# Ethernet_Interface.net
KiCad netlist of a schematic drawn in Altium Designer
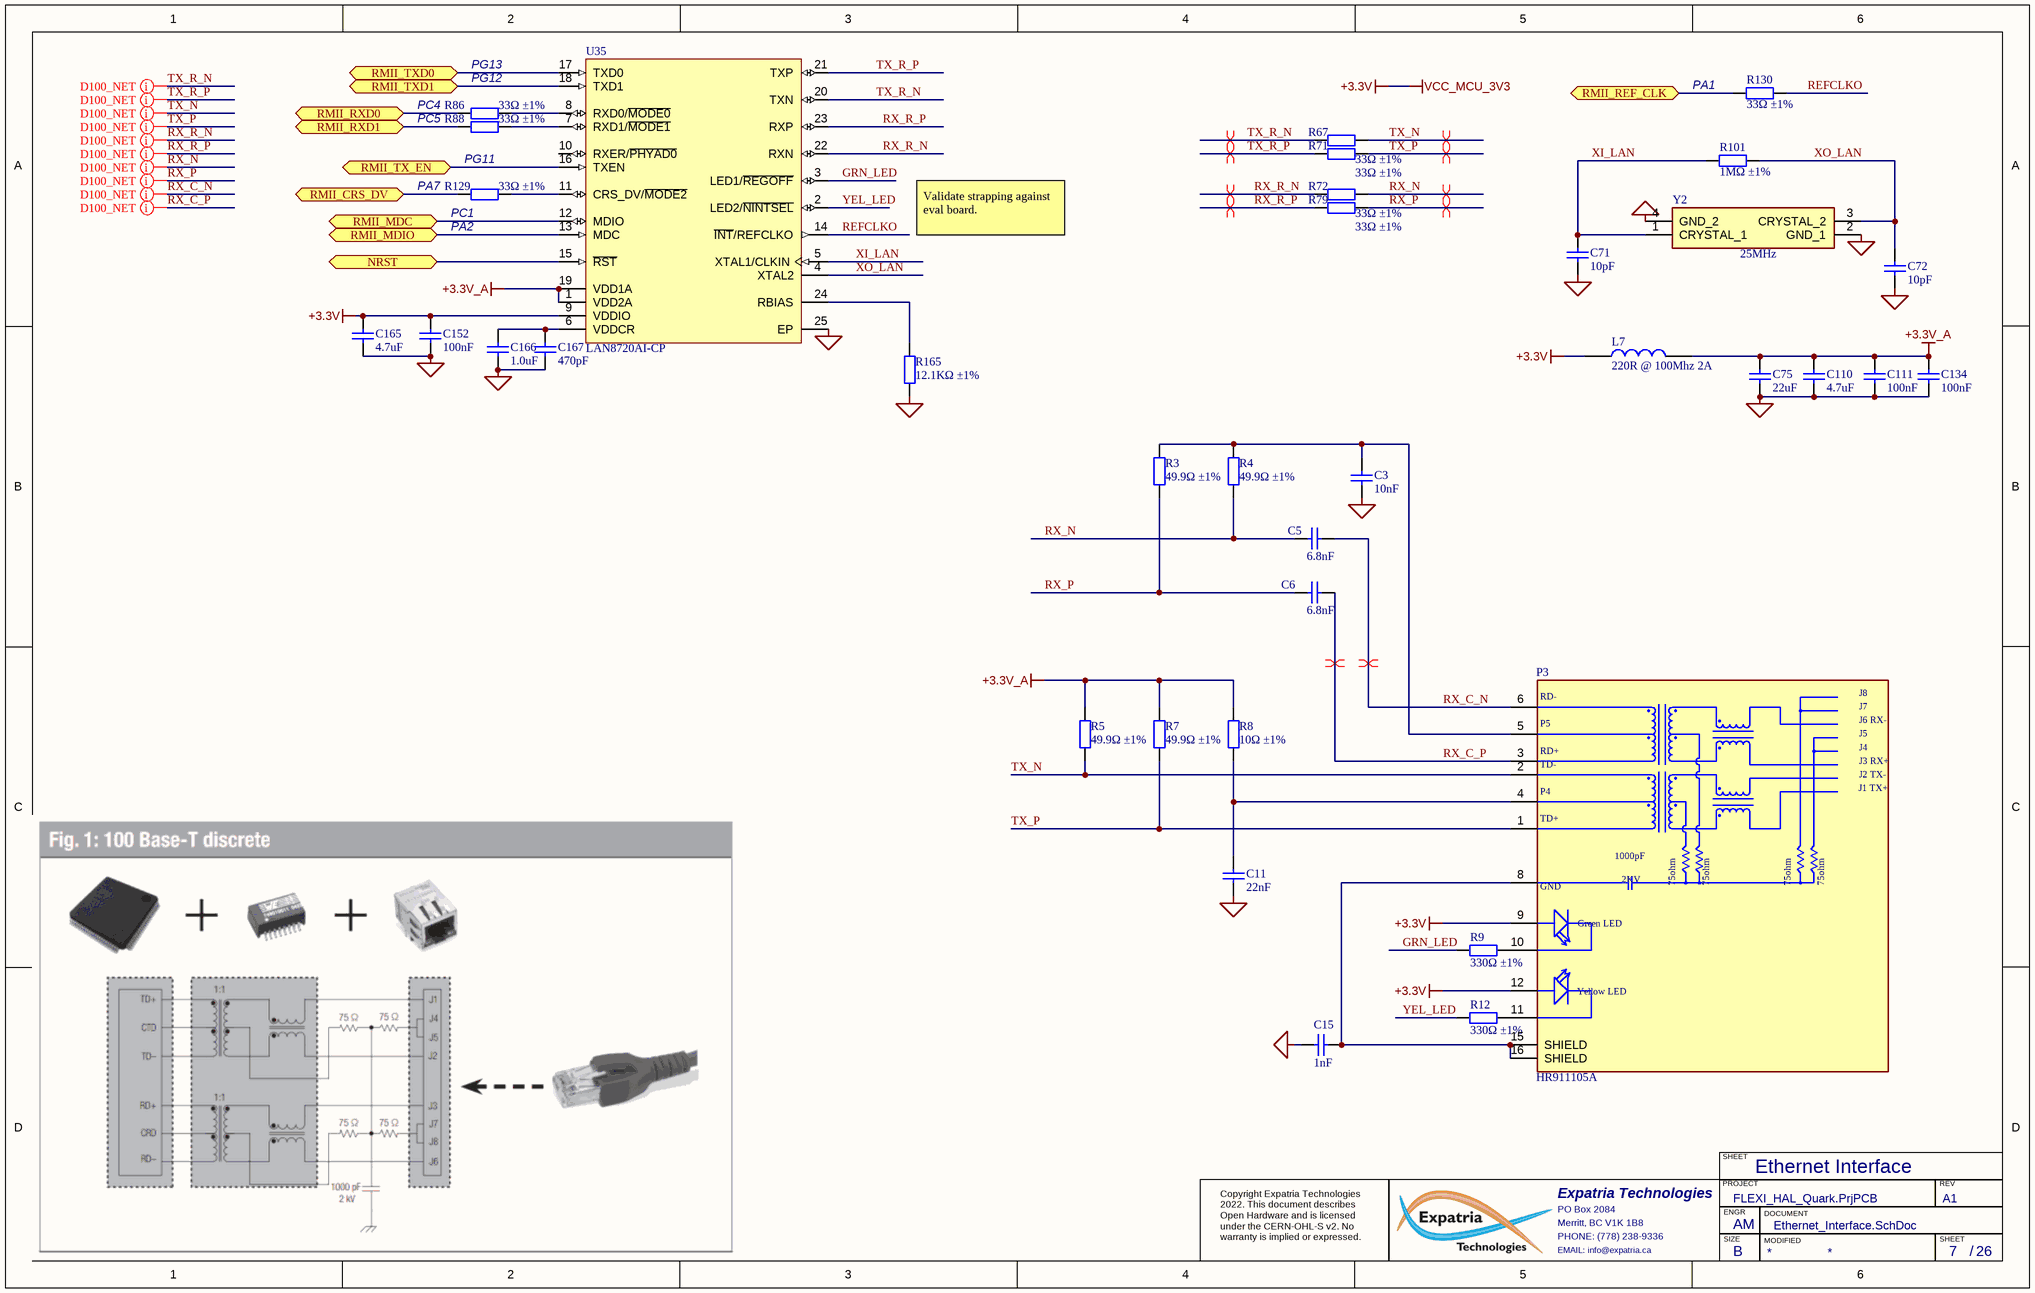
[diagram p0: Ethernet_Interface.SchDoc]

(export (version "E")
  (design (tool "Eeschema 10.0.6"))
  (components
    (comp (ref "C3")
      (value "10nF")
      (footprint "0402_C")
      (description "Chip capacitors")
      (fields
        (field (name "MANUFACTURER") "Samsung Electro-Mechanics")
        (field (name "MANUFACTURER PART NUMBER") "CL05B103KB5NNNC")
      )
      (libsource (lib "Cap") (part "0402 10nF (103) 10% 50V"))
    )
    (comp (ref "C5")
      (value "6.8nF")
      (footprint "0402_C")
      (description "Chip capacitors")
      (fields
        (field (name "MANUFACTURER") "Guangdong Fenghua Advanced Tech")
        (field (name "MANUFACTURER PART NUMBER") "0402B682K500NT")
      )
      (libsource (lib "Cap") (part "0402 6.8nF (682) 10% 50V"))
    )
    (comp (ref "C6")
      (value "6.8nF")
      (footprint "0402_C")
      (description "Chip capacitors")
      (fields
        (field (name "MANUFACTURER") "Guangdong Fenghua Advanced Tech")
        (field (name "MANUFACTURER PART NUMBER") "0402B682K500NT")
      )
      (libsource (lib "Cap") (part "0402 6.8nF (682) 10% 50V"))
    )
    (comp (ref "C11")
      (value "22nF")
      (footprint "0402_C")
      (description "Chip capacitors")
      (fields
        (field (name "MANUFACTURER") "Guangdong Fenghua Advanced Tech")
        (field (name "MANUFACTURER PART NUMBER") "0402B223K500NT")
      )
      (libsource (lib "Cap") (part "0402 22nF (223) 10% 50V"))
    )
    (comp (ref "C15")
      (value "1nF")
      (footprint "1206_C")
      (description "Chip capacitors")
      (fields
        (field (name "MANUFACTURER") "Samsung Electro-Mechanics")
        (field (name "MANUFACTURER PART NUMBER") "CL31B102KGFNNNE")
      )
      (libsource (lib "Cap") (part "1206 1nF (102) 10% 500V"))
    )
    (comp (ref "C71")
      (value "10pF")
      (footprint "0402_C")
      (description "Chip capacitors")
      (fields
        (field (name "MANUFACTURER") "Samsung Electro-Mechanics")
        (field (name "MANUFACTURER PART NUMBER") "CL05C100JB5NNNC")
      )
      (libsource (lib "Cap") (part "0402 10pF (100) 5% 50V"))
    )
    (comp (ref "C72")
      (value "10pF")
      (footprint "0402_C")
      (description "Chip capacitors")
      (fields
        (field (name "MANUFACTURER") "Samsung Electro-Mechanics")
        (field (name "MANUFACTURER PART NUMBER") "CL05C100JB5NNNC")
      )
      (libsource (lib "Cap") (part "0402 10pF (100) 5% 50V"))
    )
    (comp (ref "C75")
      (value "22uF")
      (footprint "0805_C")
      (description "25V 22uF X5R ±20% 0805 Multilayer Ceramic Capacitors MLCC - SMD/SMT ROHS")
      (fields (field (name "MANUFACTURER") "Samsung Electro-Mechanics") (field (name "TOLERANCE") "20%"))
      (libsource (lib "Sienci_Labs") (part "0805 22uF (226) 20% 25V"))
    )
    (comp (ref "C110")
      (value "4.7uF")
      (footprint "0603_C")
      (description "16V 4.7uF X5R ±10% 0603 Multilayer Ceramic Capacitors MLCC - SMD/SMT ROHS")
      (fields (field (name "MANUFACTURER") "Samsung Electro-Mechanics") (field (name "TOLERANCE") "10%"))
      (libsource (lib "Sienci_Labs") (part "0603 4.7uF (475) 10% 16V"))
    )
    (comp (ref "C111")
      (value "100nF")
      (footprint "0402_C")
      (description "16V 100nF X7R ±10% 0402 Multilayer Ceramic Capacitors MLCC - SMD/SMT ROHS")
      (fields (field (name "MANUFACTURER") "Samsung Electro-Mechanics") (field (name "TOLERANCE") "10%"))
      (libsource (lib "Sienci_Labs") (part "0402 100nF (104) 10% 16V"))
    )
    (comp (ref "C134")
      (value "100nF")
      (footprint "0402_C")
      (description "16V 100nF X7R ±10% 0402 Multilayer Ceramic Capacitors MLCC - SMD/SMT ROHS")
      (fields (field (name "MANUFACTURER") "Samsung Electro-Mechanics") (field (name "TOLERANCE") "10%"))
      (libsource (lib "Sienci_Labs") (part "0402 100nF (104) 10% 16V"))
    )
    (comp (ref "C152")
      (value "100nF")
      (footprint "0402_C")
      (description "16V 100nF X7R ±10% 0402 Multilayer Ceramic Capacitors MLCC - SMD/SMT ROHS")
      (fields (field (name "MANUFACTURER") "Samsung Electro-Mechanics") (field (name "TOLERANCE") "10%"))
      (libsource (lib "Sienci_Labs") (part "0402 100nF (104) 10% 16V"))
    )
    (comp (ref "C165")
      (value "4.7uF")
      (footprint "0603_C")
      (description "16V 4.7uF X5R ±10% 0603 Multilayer Ceramic Capacitors MLCC - SMD/SMT ROHS")
      (fields (field (name "MANUFACTURER") "Samsung Electro-Mechanics") (field (name "TOLERANCE") "10%"))
      (libsource (lib "Sienci_Labs") (part "0603 4.7uF (475) 10% 16V"))
    )
    (comp (ref "C166")
      (value "1.0uF")
      (footprint "0402_C")
      (description "Chip capacitor")
      (fields
        (field (name "MANUFACTURER") "Samsung Electro-Mechanics")
        (field (name "PARTNUMBER") "CL05A105KA5NQNC")
      )
      (libsource (lib "Cap") (part "0402 1.0uF (105) 10% 25V"))
    )
    (comp (ref "C167")
      (value "470pF")
      (footprint "0402_C")
      (description "Chip capacitors")
      (fields
        (field (name "MANUFACTURER") "Guangdong Fenghua Advanced Tech")
        (field (name "PARTNUMBER") "0402B471K500NT")
      )
      (libsource (lib "Cap") (part "0402 470pF (471) 10% 50V"))
    )
    (comp (ref "L7")
      (value "220R @ 100Mhz 2A")
      (footprint "0805_R")
      (description "150mΩ ±25% 220Ω@100MHz 0805 Ferrite Beads ROHS")
      (fields
        (field (name "MANUFACTURER PART NUMBER") "CBW201209U221T")
        (field (name "MANUFACTURER") "FH (Guangdong Fenghua Advanced Tech)")
      )
      (libsource (lib "Sienci_Labs") (part "CBW201209U221T"))
    )
    (comp (ref "P3")
      (value "HR911105A")
      (footprint "HANRUN_HR911105A")
      (description "HR911105A Ethernet Interface Arduino Platform Evaluation Expansion Board")
      (fields (field (name "MANUFACTURER") "DFRobot"))
      (libsource (lib "Sienci_Labs") (part "HR911105A"))
    )
    (comp (ref "R3")
      (value "49.9Ω ±1%")
      (footprint "0402_R")
      (description "Chip resistor")
      (fields
        (field (name "MANUFACTURER") "Uniroyal Elec")
        (field (name "MANUFACTURER PART NUMBER") "0402WGF499JTCE")
      )
      (libsource (lib "RES") (part "0402 49.9R (49R9) 1%"))
    )
    (comp (ref "R4")
      (value "49.9Ω ±1%")
      (footprint "0402_R")
      (description "Chip resistor")
      (fields
        (field (name "MANUFACTURER") "Uniroyal Elec")
        (field (name "MANUFACTURER PART NUMBER") "0402WGF499JTCE")
      )
      (libsource (lib "RES") (part "0402 49.9R (49R9) 1%"))
    )
    (comp (ref "R5")
      (value "49.9Ω ±1%")
      (footprint "0402_R")
      (description "Chip resistor")
      (fields
        (field (name "MANUFACTURER") "Uniroyal Elec")
        (field (name "MANUFACTURER PART NUMBER") "0402WGF499JTCE")
      )
      (libsource (lib "RES") (part "0402 49.9R (49R9) 1%"))
    )
    (comp (ref "R7")
      (value "49.9Ω ±1%")
      (footprint "0402_R")
      (description "Chip resistor")
      (fields
        (field (name "MANUFACTURER") "Uniroyal Elec")
        (field (name "MANUFACTURER PART NUMBER") "0402WGF499JTCE")
      )
      (libsource (lib "RES") (part "0402 49.9R (49R9) 1%"))
    )
    (comp (ref "R8")
      (value "10Ω ±1%")
      (footprint "0402_R")
      (description "Chip resistor")
      (fields
        (field (name "MANUFACTURER") "Uniroyal Elec")
        (field (name "MANUFACTURER PART NUMBER") "0402WGF100JTCE")
      )
      (libsource (lib "RES") (part "0402 10R (10R0) 1%"))
    )
    (comp (ref "R9")
      (value "330Ω ±1%")
      (footprint "0402_R")
      (description "Chip resistor")
      (fields
        (field (name "MANUFACTURER") "Uniroyal Elec")
        (field (name "MANUFACTURER PART NUMBER") "0402WGF3300TCE")
      )
      (libsource (lib "RES") (part "0402 330R (3300) 1%"))
    )
    (comp (ref "R12")
      (value "330Ω ±1%")
      (footprint "0402_R")
      (description "Chip resistor")
      (fields
        (field (name "MANUFACTURER") "Uniroyal Elec")
        (field (name "MANUFACTURER PART NUMBER") "0402WGF3300TCE")
      )
      (libsource (lib "RES") (part "0402 330R (3300) 1%"))
    )
    (comp (ref "R67")
      (value "33Ω ±1%")
      (footprint "0402_R")
      (description "Chip resistor")
      (fields
        (field (name "MANUFACTURER") "Uniroyal Elec")
        (field (name "MANUFACTURER PART NUMBER") "0402WGF330JTCE")
      )
      (libsource (lib "RES") (part "0402 33R (33R0) 1%"))
    )
    (comp (ref "R71")
      (value "33Ω ±1%")
      (footprint "0402_R")
      (description "Chip resistor")
      (fields
        (field (name "MANUFACTURER") "Uniroyal Elec")
        (field (name "MANUFACTURER PART NUMBER") "0402WGF330JTCE")
      )
      (libsource (lib "RES") (part "0402 33R (33R0) 1%"))
    )
    (comp (ref "R72")
      (value "33Ω ±1%")
      (footprint "0402_R")
      (description "Chip resistor")
      (fields
        (field (name "MANUFACTURER") "Uniroyal Elec")
        (field (name "MANUFACTURER PART NUMBER") "0402WGF330JTCE")
      )
      (libsource (lib "RES") (part "0402 33R (33R0) 1%"))
    )
    (comp (ref "R79")
      (value "33Ω ±1%")
      (footprint "0402_R")
      (description "Chip resistor")
      (fields
        (field (name "MANUFACTURER") "Uniroyal Elec")
        (field (name "MANUFACTURER PART NUMBER") "0402WGF330JTCE")
      )
      (libsource (lib "RES") (part "0402 33R (33R0) 1%"))
    )
    (comp (ref "R86")
      (value "33Ω ±1%")
      (footprint "0402_R")
      (description "Chip resistor")
      (fields
        (field (name "MANUFACTURER") "Uniroyal Elec")
        (field (name "MANUFACTURER PART NUMBER") "0402WGF330JTCE")
      )
      (libsource (lib "") (part "0402 33R (33R0) 1%_1"))
    )
    (comp (ref "R88")
      (value "33Ω ±1%")
      (footprint "0402_R")
      (description "Chip resistor")
      (fields
        (field (name "MANUFACTURER") "Uniroyal Elec")
        (field (name "MANUFACTURER PART NUMBER") "0402WGF330JTCE")
      )
      (libsource (lib "") (part "0402 33R (33R0) 1%_1"))
    )
    (comp (ref "R101")
      (value "1MΩ ±1%")
      (footprint "0402_R")
      (description "Chip resistor")
      (fields
        (field (name "MANUFACTURER") "Uniroyal Elec")
        (field (name "MANUFACTURER PART NUMBER") "0402WGF1004TCE")
      )
      (libsource (lib "RES") (part "0402 1M (1004) 1%"))
    )
    (comp (ref "R129")
      (value "33Ω ±1%")
      (footprint "0402_R")
      (description "Chip resistor")
      (fields
        (field (name "MANUFACTURER") "Uniroyal Elec")
        (field (name "MANUFACTURER PART NUMBER") "0402WGF330JTCE")
      )
      (libsource (lib "") (part "0402 33R (33R0) 1%_1"))
    )
    (comp (ref "R130")
      (value "33Ω ±1%")
      (footprint "0402_R")
      (description "Chip resistor")
      (fields
        (field (name "MANUFACTURER") "Uniroyal Elec")
        (field (name "MANUFACTURER PART NUMBER") "0402WGF330JTCE")
      )
      (libsource (lib "") (part "0402 33R (33R0) 1%_1"))
    )
    (comp (ref "R165")
      (value "12.1KΩ ±1%")
      (footprint "0805_R")
      (description "Chip resistor")
      (fields (field (name "MANUFACTURER") "Uniroyal Elec") (field (name "POWER") "1/8W"))
      (libsource (lib "RES") (part "0805 12.1K (1212) 1%"))
    )
    (comp (ref "U35")
      (value "LAN8720AI-CP")
      (footprint "MCHP-QFN-24_V")
      (description "RMII 10/100 Ethernet Transceiver with HP Auto-MDIX Support, -40 to 85 degC, 24-Pin QFN, RoHS, Tray")
      (fields (field (name "MANUFACTURER") "Microchip"))
      (libsource (lib "Altium Content Vault") (part "MCHP-LAN8720AX"))
    )
    (comp (ref "Y2")
      (value "25MHz")
      (footprint "YSX321SL")
      (description "25MHz SMD Crystal Resonator 20pF ±10ppm ±30ppm -40℃~+85℃ SMD3225-4P Crystals ROHS")
      (fields
        (field (name "MANUFACTURER") "Yangxing Tech")
        (field (name "MANUFACTURER PART NUMBER") "X322525MSB4SI")
      )
      (libsource (lib "Sienci_Labs") (part "X322525MSB4SI"))
    )
  )
  (nets
    (net (code "1") (name "+3.3V") (class "Default")
      (node (ref "C152") (pin "2") (pinfunction "2_2") (pintype "passive"))
      (node (ref "C165") (pin "2") (pinfunction "2_2") (pintype "passive"))
      (node (ref "L7") (pin "1") (pinfunction "1_1") (pintype "passive"))
      (node (ref "P3") (pin "12") (pinfunction "YA_12") (pintype "passive"))
      (node (ref "P3") (pin "9") (pinfunction "GA_9") (pintype "passive"))
      (node (ref "U35") (pin "9") (pinfunction "VDDIO_9") (pintype "power_in"))
    )
    (net (code "2") (name "+3.3V_A") (class "Default")
      (node (ref "C110") (pin "2") (pinfunction "2_2") (pintype "passive"))
      (node (ref "C111") (pin "2") (pinfunction "2_2") (pintype "passive"))
      (node (ref "C134") (pin "2") (pinfunction "2_2") (pintype "passive"))
      (node (ref "C75") (pin "2") (pinfunction "2_2") (pintype "passive"))
      (node (ref "L7") (pin "2") (pinfunction "2_2") (pintype "passive"))
      (node (ref "R5") (pin "1") (pinfunction "1_1") (pintype "passive"))
      (node (ref "R7") (pin "1") (pinfunction "1_1") (pintype "passive"))
      (node (ref "R8") (pin "1") (pinfunction "1_1") (pintype "passive"))
      (node (ref "U35") (pin "1") (pinfunction "VDD2A_1") (pintype "power_in"))
      (node (ref "U35") (pin "19") (pinfunction "VDD1A_19") (pintype "power_in"))
    )
    (net (code "3") (name "/GRN_LED") (class "Default")
      (node (ref "R9") (pin "1") (pinfunction "1_1") (pintype "passive"))
      (node (ref "U35") (pin "3") (pinfunction "LED1/~{REGOFF}_3") (pintype "bidirectional"))
    )
    (net (code "4") (name "/NRST") (class "Default")
      (node (ref "U35") (pin "15") (pinfunction "~{RST}_15") (pintype "input"))
    )
    (net (code "5") (name "/REFCLKO") (class "Default")
      (node (ref "R130") (pin "2") (pinfunction "2_2") (pintype "passive"))
      (node (ref "U35") (pin "14") (pinfunction "~{INT}/REFCLKO_14") (pintype "output"))
    )
    (net (code "6") (name "/RMII_CRS_DV") (class "Default")
      (node (ref "R129") (pin "1") (pinfunction "1_1") (pintype "passive"))
    )
    (net (code "7") (name "/RMII_MDC") (class "Default")
      (node (ref "U35") (pin "12") (pinfunction "MDIO_12") (pintype "bidirectional"))
    )
    (net (code "8") (name "/RMII_MDIO") (class "Default")
      (node (ref "U35") (pin "13") (pinfunction "MDC_13") (pintype "input"))
    )
    (net (code "9") (name "/RMII_REF_CLK") (class "Default")
      (node (ref "R130") (pin "1") (pinfunction "1_1") (pintype "passive"))
    )
    (net (code "10") (name "/RMII_RXD0") (class "Default")
      (node (ref "R86") (pin "1") (pinfunction "1_1") (pintype "passive"))
    )
    (net (code "11") (name "/RMII_RXD1") (class "Default")
      (node (ref "R88") (pin "1") (pinfunction "1_1") (pintype "passive"))
    )
    (net (code "12") (name "/RMII_TXD0") (class "Default")
      (node (ref "U35") (pin "17") (pinfunction "TXD0_17") (pintype "input"))
    )
    (net (code "13") (name "/RMII_TXD1") (class "Default")
      (node (ref "U35") (pin "18") (pinfunction "TXD1_18") (pintype "input"))
    )
    (net (code "14") (name "/RMII_TX_EN") (class "Default")
      (node (ref "U35") (pin "16") (pinfunction "TXEN_16") (pintype "input"))
    )
    (net (code "15") (name "/RX_C_N") (class "Default")
      (node (ref "C5") (pin "1") (pinfunction "1_1") (pintype "passive"))
      (node (ref "P3") (pin "6") (pinfunction "RD-_6") (pintype "passive"))
    )
    (net (code "16") (name "/RX_C_P") (class "Default")
      (node (ref "C6") (pin "1") (pinfunction "1_1") (pintype "passive"))
      (node (ref "P3") (pin "3") (pinfunction "RD+_3") (pintype "passive"))
    )
    (net (code "17") (name "/RX_N") (class "Default")
      (node (ref "C5") (pin "2") (pinfunction "2_2") (pintype "passive"))
      (node (ref "R4") (pin "2") (pinfunction "2_2") (pintype "passive"))
      (node (ref "R72") (pin "1") (pinfunction "1_1") (pintype "passive"))
    )
    (net (code "18") (name "/RX_P") (class "Default")
      (node (ref "C6") (pin "2") (pinfunction "2_2") (pintype "passive"))
      (node (ref "R3") (pin "2") (pinfunction "2_2") (pintype "passive"))
      (node (ref "R79") (pin "1") (pinfunction "1_1") (pintype "passive"))
    )
    (net (code "19") (name "/RX_R_N") (class "Default")
      (node (ref "R72") (pin "2") (pinfunction "2_2") (pintype "passive"))
      (node (ref "U35") (pin "22") (pinfunction "RXN_22") (pintype "bidirectional"))
    )
    (net (code "20") (name "/RX_R_P") (class "Default")
      (node (ref "R79") (pin "2") (pinfunction "2_2") (pintype "passive"))
      (node (ref "U35") (pin "23") (pinfunction "RXP_23") (pintype "bidirectional"))
    )
    (net (code "21") (name "/TX_N") (class "Default")
      (node (ref "P3") (pin "2") (pinfunction "TD-_2") (pintype "passive"))
      (node (ref "R5") (pin "2") (pinfunction "2_2") (pintype "passive"))
      (node (ref "R67") (pin "1") (pinfunction "1_1") (pintype "passive"))
    )
    (net (code "22") (name "/TX_P") (class "Default")
      (node (ref "P3") (pin "1") (pinfunction "TD+_1") (pintype "passive"))
      (node (ref "R7") (pin "2") (pinfunction "2_2") (pintype "passive"))
      (node (ref "R71") (pin "1") (pinfunction "1_1") (pintype "passive"))
    )
    (net (code "23") (name "/TX_R_N") (class "Default")
      (node (ref "R67") (pin "2") (pinfunction "2_2") (pintype "passive"))
      (node (ref "U35") (pin "20") (pinfunction "TXN_20") (pintype "bidirectional"))
    )
    (net (code "24") (name "/TX_R_P") (class "Default")
      (node (ref "R71") (pin "2") (pinfunction "2_2") (pintype "passive"))
      (node (ref "U35") (pin "21") (pinfunction "TXP_21") (pintype "bidirectional"))
    )
    (net (code "25") (name "/XI_LAN") (class "Default")
      (node (ref "C71") (pin "2") (pinfunction "2_2") (pintype "passive"))
      (node (ref "R101") (pin "1") (pinfunction "1_1") (pintype "passive"))
      (node (ref "U35") (pin "5") (pinfunction "XTAL1/CLKIN_5") (pintype "input"))
      (node (ref "Y2") (pin "1") (pinfunction "CRYSTAL_1_1") (pintype "passive"))
    )
    (net (code "26") (name "/XO_LAN") (class "Default")
      (node (ref "C72") (pin "2") (pinfunction "2_2") (pintype "passive"))
      (node (ref "R101") (pin "2") (pinfunction "2_2") (pintype "passive"))
      (node (ref "U35") (pin "4") (pinfunction "XTAL2_4") (pintype "passive"))
      (node (ref "Y2") (pin "3") (pinfunction "CRYSTAL_2_3") (pintype "passive"))
    )
    (net (code "27") (name "/YEL_LED") (class "Default")
      (node (ref "R12") (pin "1") (pinfunction "1_1") (pintype "passive"))
      (node (ref "U35") (pin "2") (pinfunction "LED2/~{NINTSEL}_2") (pintype "bidirectional"))
    )
    (net (code "28") (name "MCU_GND") (class "Default")
      (node (ref "C11") (pin "1") (pinfunction "1_1") (pintype "passive"))
      (node (ref "C110") (pin "1") (pinfunction "1_1") (pintype "passive"))
      (node (ref "C111") (pin "1") (pinfunction "1_1") (pintype "passive"))
      (node (ref "C134") (pin "1") (pinfunction "1_1") (pintype "passive"))
      (node (ref "C15") (pin "1") (pinfunction "1_1") (pintype "passive"))
      (node (ref "C152") (pin "1") (pinfunction "1_1") (pintype "passive"))
      (node (ref "C165") (pin "1") (pinfunction "1_1") (pintype "passive"))
      (node (ref "C166") (pin "1") (pinfunction "1_1") (pintype "passive"))
      (node (ref "C167") (pin "1") (pinfunction "1_1") (pintype "passive"))
      (node (ref "C3") (pin "1") (pinfunction "1_1") (pintype "passive"))
      (node (ref "C71") (pin "1") (pinfunction "1_1") (pintype "passive"))
      (node (ref "C72") (pin "1") (pinfunction "1_1") (pintype "passive"))
      (node (ref "C75") (pin "1") (pinfunction "1_1") (pintype "passive"))
      (node (ref "R165") (pin "1") (pinfunction "1_1") (pintype "passive"))
      (node (ref "U35") (pin "25") (pinfunction "EP_25") (pintype "power_in"))
      (node (ref "Y2") (pin "2") (pinfunction "GND_1_2") (pintype "passive"))
      (node (ref "Y2") (pin "4") (pinfunction "GND_2_4") (pintype "passive"))
    )
    (net (code "29") (name "Net-(P3-GC)") (class "Default")
      (node (ref "P3") (pin "10") (pinfunction "GC_10") (pintype "passive"))
      (node (ref "R9") (pin "2") (pinfunction "2_2") (pintype "passive"))
    )
    (net (code "30") (name "Net-(P3-GND)") (class "Default")
      (node (ref "C15") (pin "2") (pinfunction "2_2") (pintype "passive"))
      (node (ref "P3") (pin "15") (pinfunction "SHIELD_15") (pintype "passive"))
      (node (ref "P3") (pin "16") (pinfunction "SHIELD_16") (pintype "passive"))
      (node (ref "P3") (pin "8") (pinfunction "GND_8") (pintype "power_in"))
    )
    (net (code "31") (name "Net-(P3-P4)") (class "Default")
      (node (ref "C11") (pin "2") (pinfunction "2_2") (pintype "passive"))
      (node (ref "P3") (pin "4") (pinfunction "P4_4") (pintype "passive"))
      (node (ref "R8") (pin "2") (pinfunction "2_2") (pintype "passive"))
    )
    (net (code "32") (name "Net-(P3-P5)") (class "Default")
      (node (ref "C3") (pin "2") (pinfunction "2_2") (pintype "passive"))
      (node (ref "P3") (pin "5") (pinfunction "P5_5") (pintype "passive"))
      (node (ref "R3") (pin "1") (pinfunction "1_1") (pintype "passive"))
      (node (ref "R4") (pin "1") (pinfunction "1_1") (pintype "passive"))
    )
    (net (code "33") (name "Net-(P3-YC)") (class "Default")
      (node (ref "P3") (pin "11") (pinfunction "YC_11") (pintype "passive"))
      (node (ref "R12") (pin "2") (pinfunction "2_2") (pintype "passive"))
    )
    (net (code "34") (name "Net-(U35-CRS_DV{slash}~{MODE2})") (class "Default")
      (node (ref "R129") (pin "2") (pinfunction "2_2") (pintype "passive"))
      (node (ref "U35") (pin "11") (pinfunction "CRS_DV/~{MODE2}_11") (pintype "bidirectional"))
    )
    (net (code "35") (name "Net-(U35-RBIAS)") (class "Default")
      (node (ref "R165") (pin "2") (pinfunction "2_2") (pintype "passive"))
      (node (ref "U35") (pin "24") (pinfunction "RBIAS_24") (pintype "passive"))
    )
    (net (code "36") (name "Net-(U35-RXD0{slash}~{MODE0})") (class "Default")
      (node (ref "R86") (pin "2") (pinfunction "2_2") (pintype "passive"))
      (node (ref "U35") (pin "8") (pinfunction "RXD0/~{MODE0}_8") (pintype "bidirectional"))
    )
    (net (code "37") (name "Net-(U35-RXD1{slash}~{MODE1})") (class "Default")
      (node (ref "R88") (pin "2") (pinfunction "2_2") (pintype "passive"))
      (node (ref "U35") (pin "7") (pinfunction "RXD1/~{MODE1}_7") (pintype "bidirectional"))
    )
    (net (code "38") (name "Net-(U35-VDDCR)") (class "Default")
      (node (ref "C166") (pin "2") (pinfunction "2_2") (pintype "passive"))
      (node (ref "C167") (pin "2") (pinfunction "2_2") (pintype "passive"))
      (node (ref "U35") (pin "6") (pinfunction "VDDCR_6") (pintype "power_in"))
    )
    (net (code "39") (name "unconnected-(U35-RXER{slash}~{PHYAD0}-Pad10)") (class "Default")
      (node (ref "U35") (pin "10") (pinfunction "RXER/~{PHYAD0}_10") (pintype "bidirectional"))
    )
  )
)
